# logic_sdram.net
KiCad netlist of a schematic drawn in Altium Designer
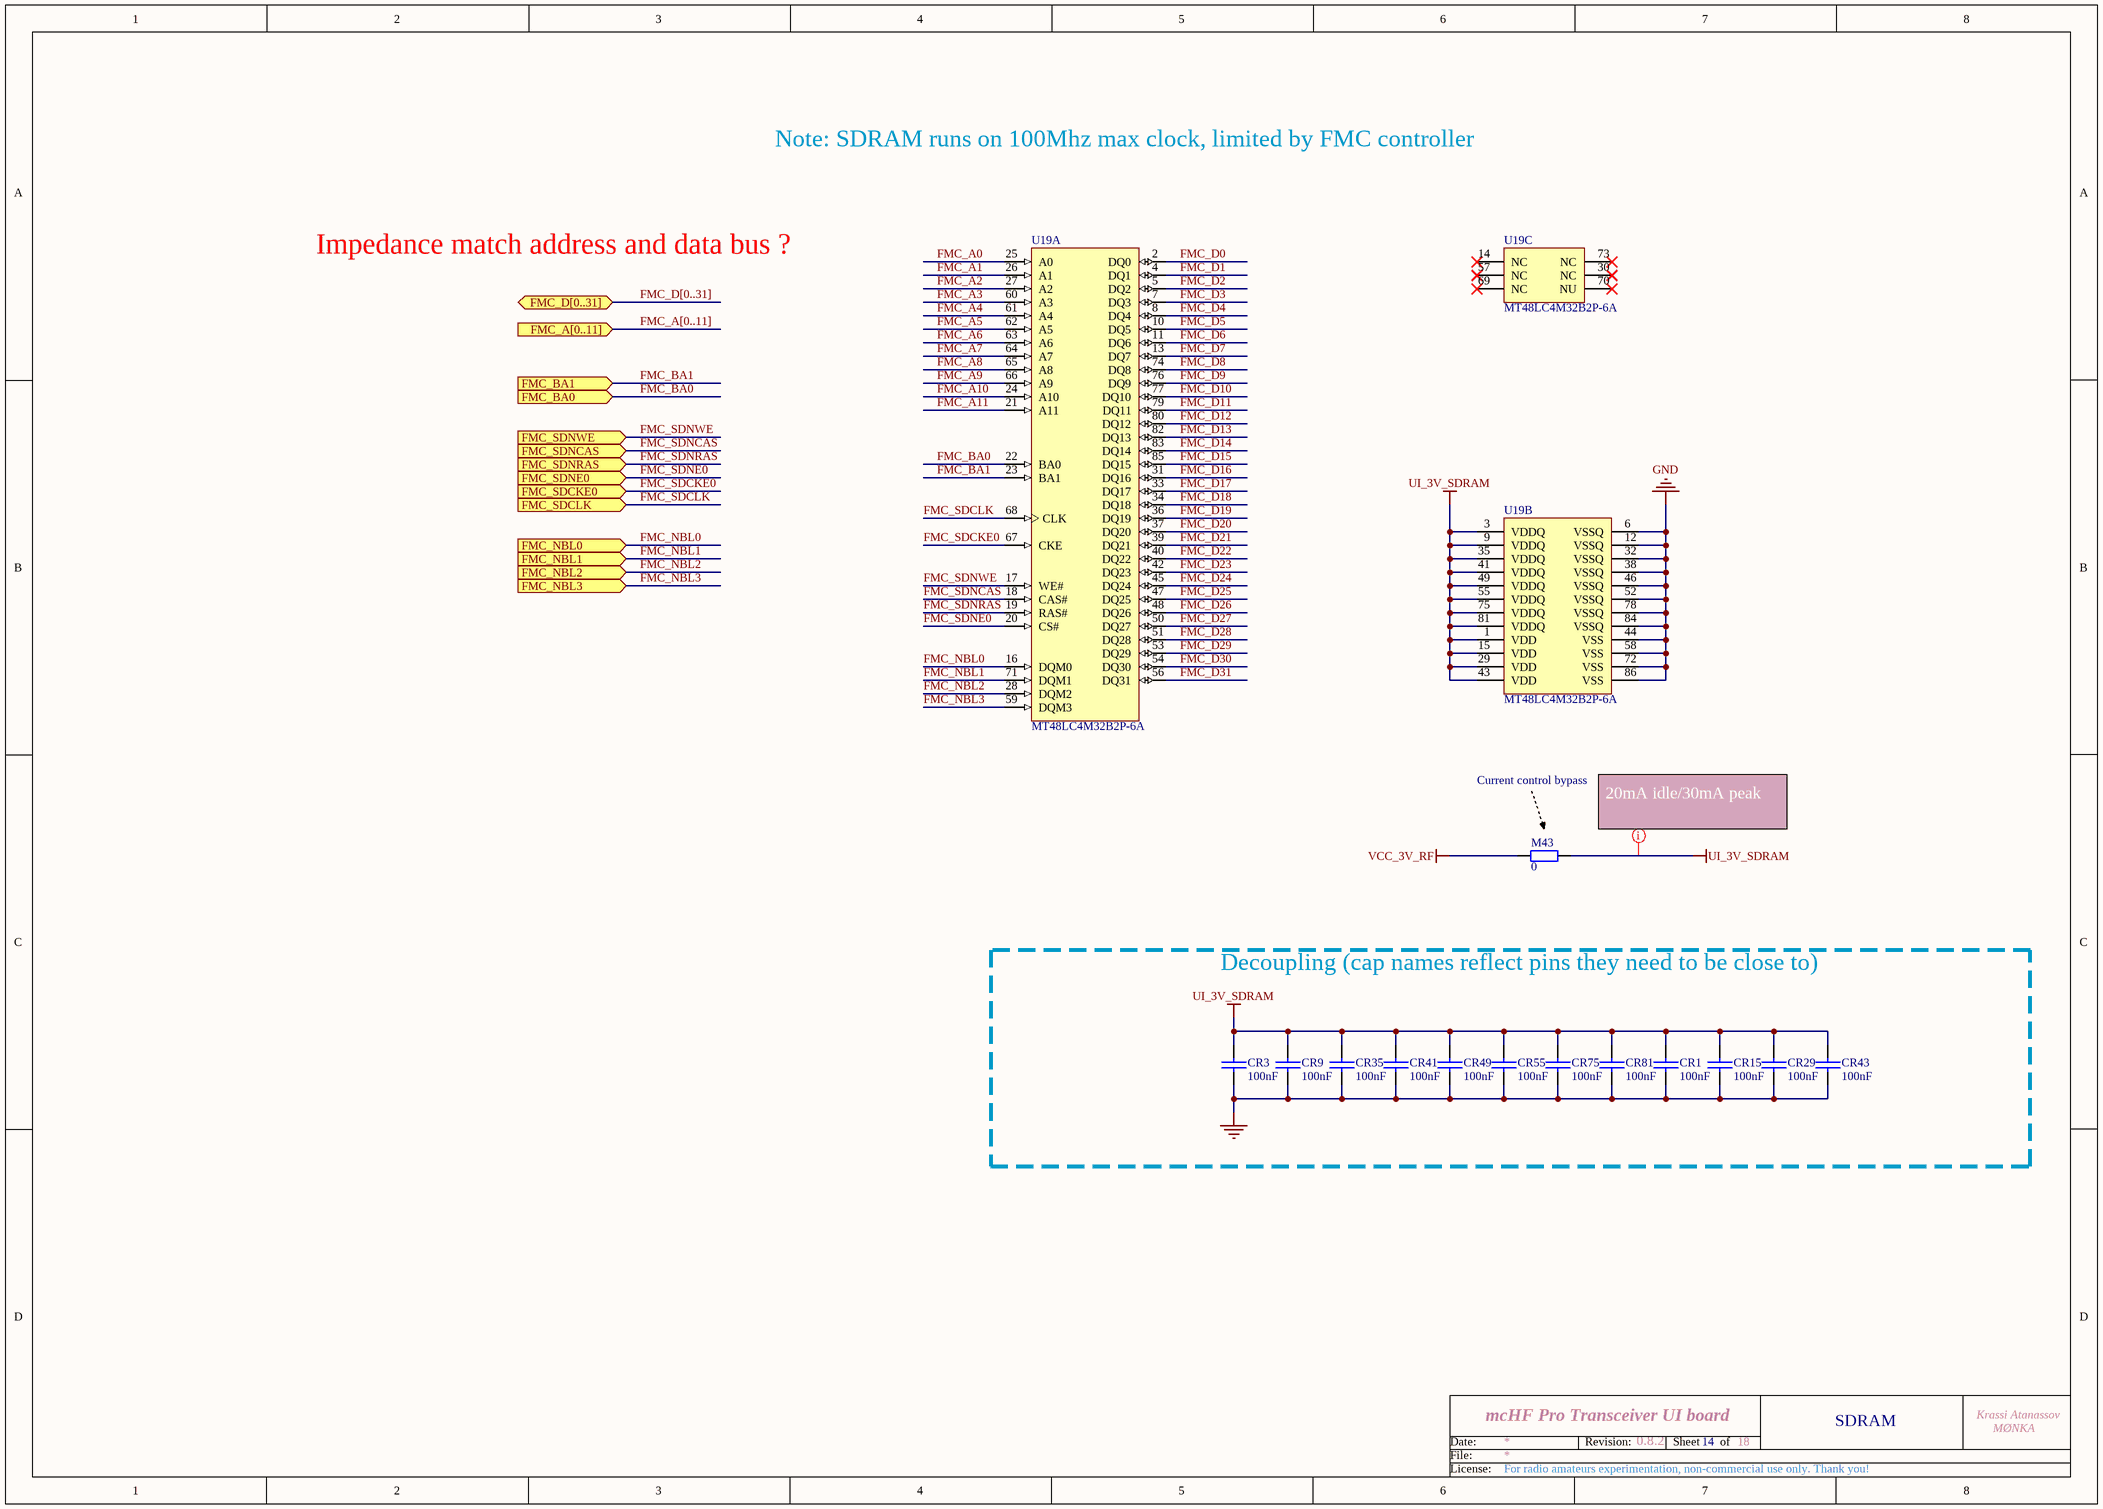
[diagram p0: logic_sdram.SchDoc]

(export (version "E")
  (design (tool "Eeschema 10.0.6"))
  (components
    (comp (ref "CR1")
      (value "100nF")
      (footprint "0805")
      (description "Capacitor")
      (libsource (lib "mcHF_ui") (part "CAP"))
    )
    (comp (ref "CR3")
      (value "100nF")
      (footprint "0805")
      (description "Capacitor")
      (libsource (lib "mcHF_ui") (part "CAP"))
    )
    (comp (ref "CR9")
      (value "100nF")
      (footprint "0805")
      (description "Capacitor")
      (libsource (lib "mcHF_ui") (part "CAP"))
    )
    (comp (ref "CR15")
      (value "100nF")
      (footprint "0805")
      (description "Capacitor")
      (libsource (lib "mcHF_ui") (part "CAP"))
    )
    (comp (ref "CR29")
      (value "100nF")
      (footprint "0805")
      (description "Capacitor")
      (libsource (lib "mcHF_ui") (part "CAP"))
    )
    (comp (ref "CR35")
      (value "100nF")
      (footprint "0805")
      (description "Capacitor")
      (libsource (lib "mcHF_ui") (part "CAP"))
    )
    (comp (ref "CR41")
      (value "100nF")
      (footprint "0805")
      (description "Capacitor")
      (libsource (lib "mcHF_ui") (part "CAP"))
    )
    (comp (ref "CR43")
      (value "100nF")
      (footprint "0805")
      (description "Capacitor")
      (libsource (lib "mcHF_ui") (part "CAP"))
    )
    (comp (ref "CR49")
      (value "100nF")
      (footprint "0805")
      (description "Capacitor")
      (libsource (lib "mcHF_ui") (part "CAP"))
    )
    (comp (ref "CR55")
      (value "100nF")
      (footprint "0805")
      (description "Capacitor")
      (libsource (lib "mcHF_ui") (part "CAP"))
    )
    (comp (ref "CR75")
      (value "100nF")
      (footprint "0805")
      (description "Capacitor")
      (libsource (lib "mcHF_ui") (part "CAP"))
    )
    (comp (ref "CR81")
      (value "100nF")
      (footprint "0805")
      (description "Capacitor")
      (libsource (lib "mcHF_ui") (part "CAP"))
    )
    (comp (ref "M43")
      (value "0")
      (footprint "0805")
      (description "Resistor")
      (libsource (lib "mcHF_rf") (part "RES"))
    )
    (comp (ref "U19")
      (value "MT48LC4M32B2P-6A")
      (footprint "MICT-TG-86_N")
      (description "128Mb PC133 SDR SDRAM, 4Mb x 32, 6ns, 3.3V, 0 to 70 degC, 86-Pin TSOP")
      (libsource (lib "mcHFpro_logic") (part "MT48LC4M32B2P-6A"))
    )
  )
  (nets
    (net (code "1") (name "/FMC_A0") (class "Default")
      (node (ref "U19") (pin "25") (pinfunction "A0_25") (pintype "input"))
    )
    (net (code "2") (name "/FMC_A1") (class "Default")
      (node (ref "U19") (pin "26") (pinfunction "A1_26") (pintype "input"))
    )
    (net (code "3") (name "/FMC_A2") (class "Default")
      (node (ref "U19") (pin "27") (pinfunction "A2_27") (pintype "input"))
    )
    (net (code "4") (name "/FMC_A3") (class "Default")
      (node (ref "U19") (pin "60") (pinfunction "A3_60") (pintype "input"))
    )
    (net (code "5") (name "/FMC_A4") (class "Default")
      (node (ref "U19") (pin "61") (pinfunction "A4_61") (pintype "input"))
    )
    (net (code "6") (name "/FMC_A5") (class "Default")
      (node (ref "U19") (pin "62") (pinfunction "A5_62") (pintype "input"))
    )
    (net (code "7") (name "/FMC_A6") (class "Default")
      (node (ref "U19") (pin "63") (pinfunction "A6_63") (pintype "input"))
    )
    (net (code "8") (name "/FMC_A7") (class "Default")
      (node (ref "U19") (pin "64") (pinfunction "A7_64") (pintype "input"))
    )
    (net (code "9") (name "/FMC_A8") (class "Default")
      (node (ref "U19") (pin "65") (pinfunction "A8_65") (pintype "input"))
    )
    (net (code "10") (name "/FMC_A9") (class "Default")
      (node (ref "U19") (pin "66") (pinfunction "A9_66") (pintype "input"))
    )
    (net (code "11") (name "/FMC_A10") (class "Default")
      (node (ref "U19") (pin "24") (pinfunction "A10_24") (pintype "input"))
    )
    (net (code "12") (name "/FMC_A11") (class "Default")
      (node (ref "U19") (pin "21") (pinfunction "A11_21") (pintype "input"))
    )
    (net (code "14") (name "/FMC_BA0") (class "Default")
      (node (ref "U19") (pin "22") (pinfunction "BA0_22") (pintype "input"))
    )
    (net (code "15") (name "/FMC_BA1") (class "Default")
      (node (ref "U19") (pin "23") (pinfunction "BA1_23") (pintype "input"))
    )
    (net (code "16") (name "/FMC_D0") (class "Default")
      (node (ref "U19") (pin "2") (pinfunction "DQ0_2") (pintype "bidirectional"))
    )
    (net (code "17") (name "/FMC_D1") (class "Default")
      (node (ref "U19") (pin "4") (pinfunction "DQ1_4") (pintype "bidirectional"))
    )
    (net (code "18") (name "/FMC_D2") (class "Default")
      (node (ref "U19") (pin "5") (pinfunction "DQ2_5") (pintype "bidirectional"))
    )
    (net (code "19") (name "/FMC_D3") (class "Default")
      (node (ref "U19") (pin "7") (pinfunction "DQ3_7") (pintype "bidirectional"))
    )
    (net (code "20") (name "/FMC_D4") (class "Default")
      (node (ref "U19") (pin "8") (pinfunction "DQ4_8") (pintype "bidirectional"))
    )
    (net (code "21") (name "/FMC_D5") (class "Default")
      (node (ref "U19") (pin "10") (pinfunction "DQ5_10") (pintype "bidirectional"))
    )
    (net (code "22") (name "/FMC_D6") (class "Default")
      (node (ref "U19") (pin "11") (pinfunction "DQ6_11") (pintype "bidirectional"))
    )
    (net (code "23") (name "/FMC_D7") (class "Default")
      (node (ref "U19") (pin "13") (pinfunction "DQ7_13") (pintype "bidirectional"))
    )
    (net (code "24") (name "/FMC_D8") (class "Default")
      (node (ref "U19") (pin "74") (pinfunction "DQ8_74") (pintype "bidirectional"))
    )
    (net (code "25") (name "/FMC_D9") (class "Default")
      (node (ref "U19") (pin "76") (pinfunction "DQ9_76") (pintype "bidirectional"))
    )
    (net (code "26") (name "/FMC_D10") (class "Default")
      (node (ref "U19") (pin "77") (pinfunction "DQ10_77") (pintype "bidirectional"))
    )
    (net (code "27") (name "/FMC_D11") (class "Default")
      (node (ref "U19") (pin "79") (pinfunction "DQ11_79") (pintype "bidirectional"))
    )
    (net (code "28") (name "/FMC_D12") (class "Default")
      (node (ref "U19") (pin "80") (pinfunction "DQ12_80") (pintype "bidirectional"))
    )
    (net (code "29") (name "/FMC_D13") (class "Default")
      (node (ref "U19") (pin "82") (pinfunction "DQ13_82") (pintype "bidirectional"))
    )
    (net (code "30") (name "/FMC_D14") (class "Default")
      (node (ref "U19") (pin "83") (pinfunction "DQ14_83") (pintype "bidirectional"))
    )
    (net (code "31") (name "/FMC_D15") (class "Default")
      (node (ref "U19") (pin "85") (pinfunction "DQ15_85") (pintype "bidirectional"))
    )
    (net (code "32") (name "/FMC_D16") (class "Default")
      (node (ref "U19") (pin "31") (pinfunction "DQ16_31") (pintype "bidirectional"))
    )
    (net (code "33") (name "/FMC_D17") (class "Default")
      (node (ref "U19") (pin "33") (pinfunction "DQ17_33") (pintype "bidirectional"))
    )
    (net (code "34") (name "/FMC_D18") (class "Default")
      (node (ref "U19") (pin "34") (pinfunction "DQ18_34") (pintype "bidirectional"))
    )
    (net (code "35") (name "/FMC_D19") (class "Default")
      (node (ref "U19") (pin "36") (pinfunction "DQ19_36") (pintype "bidirectional"))
    )
    (net (code "36") (name "/FMC_D20") (class "Default")
      (node (ref "U19") (pin "37") (pinfunction "DQ20_37") (pintype "bidirectional"))
    )
    (net (code "37") (name "/FMC_D21") (class "Default")
      (node (ref "U19") (pin "39") (pinfunction "DQ21_39") (pintype "bidirectional"))
    )
    (net (code "38") (name "/FMC_D22") (class "Default")
      (node (ref "U19") (pin "40") (pinfunction "DQ22_40") (pintype "bidirectional"))
    )
    (net (code "39") (name "/FMC_D23") (class "Default")
      (node (ref "U19") (pin "42") (pinfunction "DQ23_42") (pintype "bidirectional"))
    )
    (net (code "40") (name "/FMC_D24") (class "Default")
      (node (ref "U19") (pin "45") (pinfunction "DQ24_45") (pintype "bidirectional"))
    )
    (net (code "41") (name "/FMC_D25") (class "Default")
      (node (ref "U19") (pin "47") (pinfunction "DQ25_47") (pintype "bidirectional"))
    )
    (net (code "42") (name "/FMC_D26") (class "Default")
      (node (ref "U19") (pin "48") (pinfunction "DQ26_48") (pintype "bidirectional"))
    )
    (net (code "43") (name "/FMC_D27") (class "Default")
      (node (ref "U19") (pin "50") (pinfunction "DQ27_50") (pintype "bidirectional"))
    )
    (net (code "44") (name "/FMC_D28") (class "Default")
      (node (ref "U19") (pin "51") (pinfunction "DQ28_51") (pintype "bidirectional"))
    )
    (net (code "45") (name "/FMC_D29") (class "Default")
      (node (ref "U19") (pin "53") (pinfunction "DQ29_53") (pintype "bidirectional"))
    )
    (net (code "46") (name "/FMC_D30") (class "Default")
      (node (ref "U19") (pin "54") (pinfunction "DQ30_54") (pintype "bidirectional"))
    )
    (net (code "47") (name "/FMC_D31") (class "Default")
      (node (ref "U19") (pin "56") (pinfunction "DQ31_56") (pintype "bidirectional"))
    )
    (net (code "49") (name "/FMC_NBL0") (class "Default")
      (node (ref "U19") (pin "16") (pinfunction "DQM0_16") (pintype "input"))
    )
    (net (code "50") (name "/FMC_NBL1") (class "Default")
      (node (ref "U19") (pin "71") (pinfunction "DQM1_71") (pintype "input"))
    )
    (net (code "51") (name "/FMC_NBL2") (class "Default")
      (node (ref "U19") (pin "28") (pinfunction "DQM2_28") (pintype "input"))
    )
    (net (code "52") (name "/FMC_NBL3") (class "Default")
      (node (ref "U19") (pin "59") (pinfunction "DQM3_59") (pintype "input"))
    )
    (net (code "53") (name "/FMC_SDCKE0") (class "Default")
      (node (ref "U19") (pin "67") (pinfunction "CKE_67") (pintype "input"))
    )
    (net (code "54") (name "/FMC_SDCLK") (class "Default")
      (node (ref "U19") (pin "68") (pinfunction "CLK_68") (pintype "input"))
    )
    (net (code "55") (name "/FMC_SDNCAS") (class "Default")
      (node (ref "U19") (pin "18") (pinfunction "CAS#_18") (pintype "input"))
    )
    (net (code "56") (name "/FMC_SDNE0") (class "Default")
      (node (ref "U19") (pin "20") (pinfunction "CS#_20") (pintype "input"))
    )
    (net (code "57") (name "/FMC_SDNRAS") (class "Default")
      (node (ref "U19") (pin "19") (pinfunction "RAS#_19") (pintype "input"))
    )
    (net (code "58") (name "/FMC_SDNWE") (class "Default")
      (node (ref "U19") (pin "17") (pinfunction "WE#_17") (pintype "input"))
    )
    (net (code "59") (name "GND") (class "Default")
      (node (ref "CR1") (pin "2") (pinfunction "2_2") (pintype "passive"))
      (node (ref "CR15") (pin "2") (pinfunction "2_2") (pintype "passive"))
      (node (ref "CR29") (pin "2") (pinfunction "2_2") (pintype "passive"))
      (node (ref "CR3") (pin "2") (pinfunction "2_2") (pintype "passive"))
      (node (ref "CR35") (pin "2") (pinfunction "2_2") (pintype "passive"))
      (node (ref "CR41") (pin "2") (pinfunction "2_2") (pintype "passive"))
      (node (ref "CR43") (pin "2") (pinfunction "2_2") (pintype "passive"))
      (node (ref "CR49") (pin "2") (pinfunction "2_2") (pintype "passive"))
      (node (ref "CR55") (pin "2") (pinfunction "2_2") (pintype "passive"))
      (node (ref "CR75") (pin "2") (pinfunction "2_2") (pintype "passive"))
      (node (ref "CR81") (pin "2") (pinfunction "2_2") (pintype "passive"))
      (node (ref "CR9") (pin "2") (pinfunction "2_2") (pintype "passive"))
      (node (ref "U19") (pin "12") (pinfunction "VSSQ_12") (pintype "passive"))
      (node (ref "U19") (pin "32") (pinfunction "VSSQ_32") (pintype "passive"))
      (node (ref "U19") (pin "38") (pinfunction "VSSQ_38") (pintype "passive"))
      (node (ref "U19") (pin "44") (pinfunction "VSS_44") (pintype "passive"))
      (node (ref "U19") (pin "46") (pinfunction "VSSQ_46") (pintype "passive"))
      (node (ref "U19") (pin "52") (pinfunction "VSSQ_52") (pintype "passive"))
      (node (ref "U19") (pin "58") (pinfunction "VSS_58") (pintype "passive"))
      (node (ref "U19") (pin "6") (pinfunction "VSSQ_6") (pintype "passive"))
      (node (ref "U19") (pin "72") (pinfunction "VSS_72") (pintype "passive"))
      (node (ref "U19") (pin "78") (pinfunction "VSSQ_78") (pintype "passive"))
      (node (ref "U19") (pin "84") (pinfunction "VSSQ_84") (pintype "passive"))
      (node (ref "U19") (pin "86") (pinfunction "VSS_86") (pintype "passive"))
    )
    (net (code "60") (name "UI_3V_SDRAM") (class "Default")
      (node (ref "CR1") (pin "1") (pinfunction "1_1") (pintype "passive"))
      (node (ref "CR15") (pin "1") (pinfunction "1_1") (pintype "passive"))
      (node (ref "CR29") (pin "1") (pinfunction "1_1") (pintype "passive"))
      (node (ref "CR3") (pin "1") (pinfunction "1_1") (pintype "passive"))
      (node (ref "CR35") (pin "1") (pinfunction "1_1") (pintype "passive"))
      (node (ref "CR41") (pin "1") (pinfunction "1_1") (pintype "passive"))
      (node (ref "CR43") (pin "1") (pinfunction "1_1") (pintype "passive"))
      (node (ref "CR49") (pin "1") (pinfunction "1_1") (pintype "passive"))
      (node (ref "CR55") (pin "1") (pinfunction "1_1") (pintype "passive"))
      (node (ref "CR75") (pin "1") (pinfunction "1_1") (pintype "passive"))
      (node (ref "CR81") (pin "1") (pinfunction "1_1") (pintype "passive"))
      (node (ref "CR9") (pin "1") (pinfunction "1_1") (pintype "passive"))
      (node (ref "M43") (pin "2") (pinfunction "2_2") (pintype "passive"))
      (node (ref "U19") (pin "1") (pinfunction "VDD_1") (pintype "power_in"))
      (node (ref "U19") (pin "15") (pinfunction "VDD_15") (pintype "power_in"))
      (node (ref "U19") (pin "29") (pinfunction "VDD_29") (pintype "power_in"))
      (node (ref "U19") (pin "3") (pinfunction "VDDQ_3") (pintype "power_in"))
      (node (ref "U19") (pin "35") (pinfunction "VDDQ_35") (pintype "power_in"))
      (node (ref "U19") (pin "41") (pinfunction "VDDQ_41") (pintype "power_in"))
      (node (ref "U19") (pin "43") (pinfunction "VDD_43") (pintype "power_in"))
      (node (ref "U19") (pin "49") (pinfunction "VDDQ_49") (pintype "power_in"))
      (node (ref "U19") (pin "55") (pinfunction "VDDQ_55") (pintype "power_in"))
      (node (ref "U19") (pin "75") (pinfunction "VDDQ_75") (pintype "power_in"))
      (node (ref "U19") (pin "81") (pinfunction "VDDQ_81") (pintype "power_in"))
      (node (ref "U19") (pin "9") (pinfunction "VDDQ_9") (pintype "power_in"))
    )
    (net (code "61") (name "VCC_3V_RF") (class "Default")
      (node (ref "M43") (pin "1") (pinfunction "1_1") (pintype "passive"))
    )
    (net (code "62") (name "unconnected-(U19C-NC-Pad14)") (class "Default")
      (node (ref "U19") (pin "14") (pinfunction "NC_14") (pintype "passive+no_connect"))
    )
    (net (code "63") (name "unconnected-(U19C-NC-Pad30)") (class "Default")
      (node (ref "U19") (pin "30") (pinfunction "NC_30") (pintype "passive+no_connect"))
    )
    (net (code "64") (name "unconnected-(U19C-NC-Pad57)") (class "Default")
      (node (ref "U19") (pin "57") (pinfunction "NC_57") (pintype "passive+no_connect"))
    )
    (net (code "65") (name "unconnected-(U19C-NC-Pad69)") (class "Default")
      (node (ref "U19") (pin "69") (pinfunction "NC_69") (pintype "passive+no_connect"))
    )
    (net (code "66") (name "unconnected-(U19C-NC-Pad73)") (class "Default")
      (node (ref "U19") (pin "73") (pinfunction "NC_73") (pintype "passive+no_connect"))
    )
    (net (code "67") (name "unconnected-(U19C-NU-Pad70)") (class "Default")
      (node (ref "U19") (pin "70") (pinfunction "NU_70") (pintype "passive+no_connect"))
    )
  )
)
